# untitled.net
KiCad netlist of a schematic drawn in EAGLE
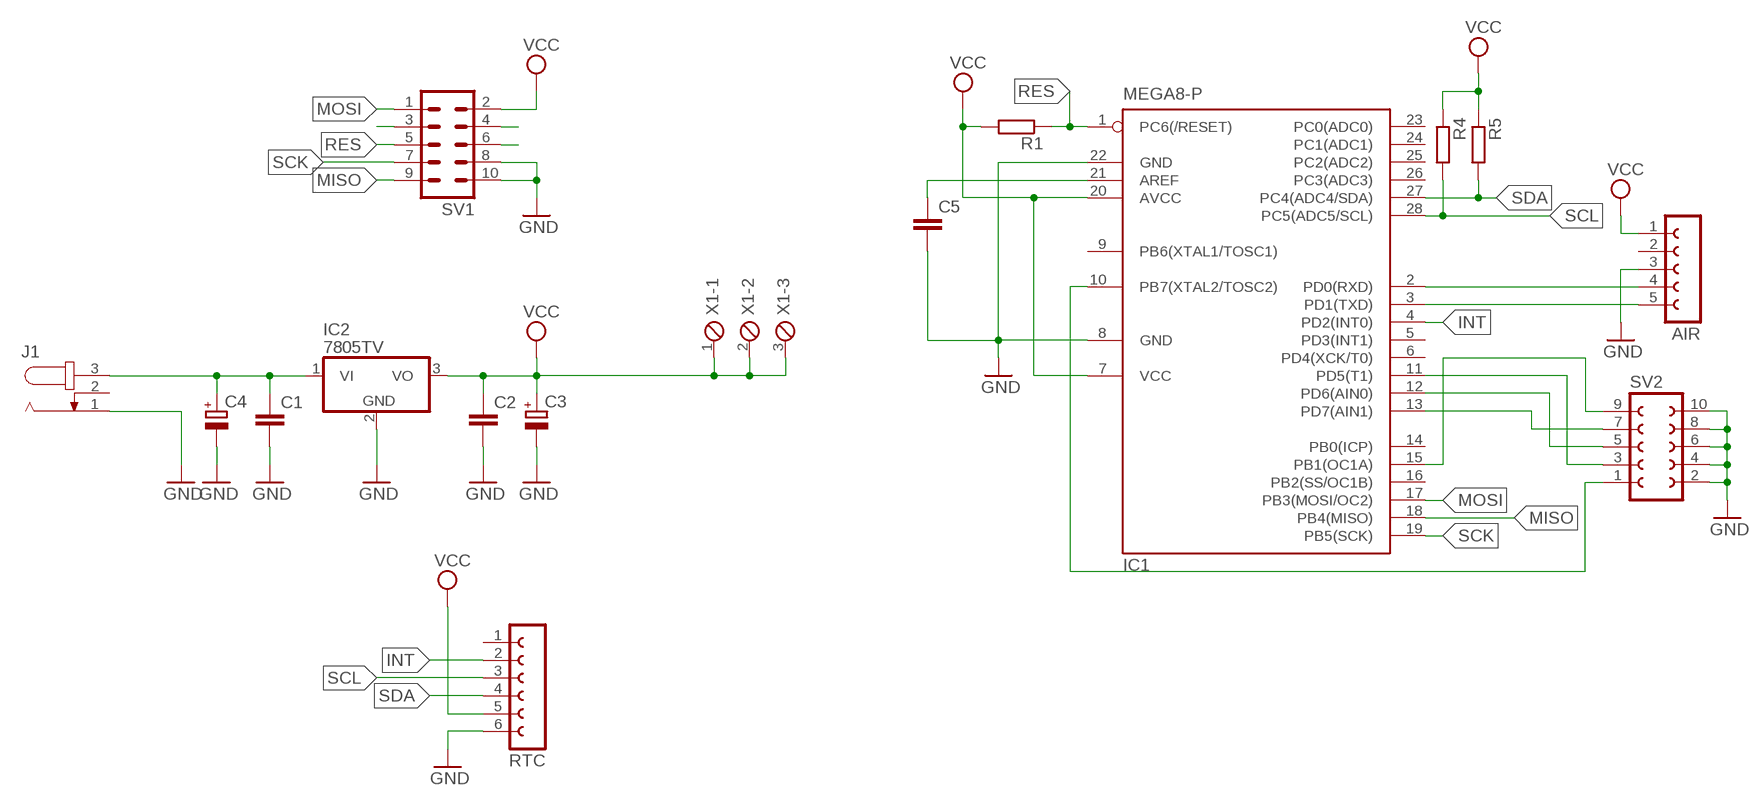
[diagram p0: schematic, sheet 1]

(export (version "E")
  (design (tool "Eeschema 10.0.6"))
  (components
    (comp (ref "AIR")
      (value "FE05-1")
      (footprint "eagle-import:FE05-1")
      (libsource (lib "eagle-import") (part "FE05-1"))
    )
    (comp (ref "C1")
      (value "C-EU025-025X050")
      (footprint "eagle-import:C025-025X050")
      (libsource (lib "eagle-import") (part "C-EU025-025X050"))
    )
    (comp (ref "C2")
      (value "C-EU025-025X050")
      (footprint "eagle-import:C025-025X050")
      (libsource (lib "eagle-import") (part "C-EU025-025X050"))
    )
    (comp (ref "C3")
      (value "CPOL-EUE2.5-5")
      (footprint "eagle-import:E2,5-5")
      (libsource (lib "eagle-import") (part "CPOL-EUE2.5-5"))
    )
    (comp (ref "C4")
      (value "CPOL-EUE3.5-8")
      (footprint "eagle-import:E3,5-8")
      (libsource (lib "eagle-import") (part "CPOL-EUE3.5-8"))
    )
    (comp (ref "C5")
      (value "C-EU025-025X050")
      (footprint "eagle-import:C025-025X050")
      (libsource (lib "eagle-import") (part "C-EU025-025X050"))
    )
    (comp (ref "IC1")
      (value "MEGA8-P")
      (footprint "eagle-import:DIL28-3")
      (libsource (lib "eagle-import") (part "MEGA8-P"))
    )
    (comp (ref "IC2")
      (value "7805TV")
      (footprint "eagle-import:TO220V")
      (libsource (lib "eagle-import") (part "78TV05"))
    )
    (comp (ref "J1")
      (value "JACK-PLUG1")
      (footprint "eagle-import:SPC4078")
      (libsource (lib "eagle-import") (part "JACK-PLUG1"))
    )
    (comp (ref "R1")
      (value "R-EU_0207/7")
      (footprint "eagle-import:0207_7")
      (libsource (lib "eagle-import") (part "R-EU_0207/7"))
    )
    (comp (ref "R4")
      (value "R-EU_0207/7")
      (footprint "eagle-import:0207_7")
      (libsource (lib "eagle-import") (part "R-EU_0207/7"))
    )
    (comp (ref "R5")
      (value "R-EU_0207/7")
      (footprint "eagle-import:0207_7")
      (libsource (lib "eagle-import") (part "R-EU_0207/7"))
    )
    (comp (ref "RTC")
      (value "FE06-1")
      (footprint "eagle-import:FE06")
      (libsource (lib "eagle-import") (part "FE06-1"))
    )
    (comp (ref "SV1")
      (value "ML10")
      (footprint "eagle-import:ML10")
      (libsource (lib "eagle-import") (part "ML10"))
    )
    (comp (ref "SV2")
      (value "FE05-2")
      (footprint "eagle-import:FE05-2")
      (libsource (lib "eagle-import") (part "FE05-2"))
    )
    (comp (ref "X1")
      (value "MPT3")
      (footprint "eagle-import:3POL254")
      (libsource (lib "eagle-import") (part "MPT3"))
    )
  )
  (nets
    (net (code "1") (name "GND") (class "Default")
      (node (ref "AIR") (pin "3") (pinfunction "3_3") (pintype "passive"))
      (node (ref "C1") (pin "2") (pinfunction "2_2") (pintype "passive"))
      (node (ref "C2") (pin "2") (pinfunction "2_2") (pintype "passive"))
      (node (ref "C3") (pin "-") (pinfunction "-_-") (pintype "passive"))
      (node (ref "C4") (pin "-") (pinfunction "-_-") (pintype "passive"))
      (node (ref "C5") (pin "2") (pinfunction "2_2") (pintype "passive"))
      (node (ref "IC1") (pin "22") (pinfunction "GND_22") (pintype "power_in"))
      (node (ref "IC1") (pin "8") (pinfunction "GND_8") (pintype "power_in"))
      (node (ref "IC2") (pin "2") (pinfunction "GND_2") (pintype "passive"))
      (node (ref "J1") (pin "1") (pinfunction "1_1") (pintype "passive"))
      (node (ref "RTC") (pin "6") (pinfunction "6_6") (pintype "passive"))
      (node (ref "SV1") (pin "10") (pinfunction "10_10") (pintype "passive"))
      (node (ref "SV1") (pin "8") (pinfunction "8_8") (pintype "passive"))
      (node (ref "SV2") (pin "10") (pinfunction "10_10") (pintype "passive"))
      (node (ref "SV2") (pin "2") (pinfunction "2_2") (pintype "passive"))
      (node (ref "SV2") (pin "4") (pinfunction "4_4") (pintype "passive"))
      (node (ref "SV2") (pin "6") (pinfunction "6_6") (pintype "passive"))
      (node (ref "SV2") (pin "8") (pinfunction "8_8") (pintype "passive"))
    )
    (net (code "2") (name "INT") (class "Default")
      (node (ref "IC1") (pin "4") (pinfunction "PD2(INT0)_4") (pintype "bidirectional"))
      (node (ref "RTC") (pin "2") (pinfunction "2_2") (pintype "passive"))
    )
    (net (code "3") (name "MISO") (class "Default")
      (node (ref "IC1") (pin "18") (pinfunction "PB4(MISO)_18") (pintype "bidirectional"))
      (node (ref "SV1") (pin "9") (pinfunction "9_9") (pintype "passive"))
    )
    (net (code "4") (name "MOSI") (class "Default")
      (node (ref "IC1") (pin "17") (pinfunction "PB3(MOSI/OC2)_17") (pintype "bidirectional"))
      (node (ref "SV1") (pin "1") (pinfunction "1_1") (pintype "passive"))
    )
    (net (code "5") (name "Net-(IC1-AREF)") (class "Default")
      (node (ref "C5") (pin "1") (pinfunction "1_1") (pintype "passive"))
      (node (ref "IC1") (pin "21") (pinfunction "AREF_21") (pintype "passive"))
    )
    (net (code "6") (name "Net-(IC1-PB1(OC1A))") (class "Default")
      (node (ref "IC1") (pin "15") (pinfunction "PB1(OC1A)_15") (pintype "bidirectional"))
      (node (ref "SV2") (pin "9") (pinfunction "9_9") (pintype "passive"))
    )
    (net (code "7") (name "Net-(IC1-PB7(XTAL2{slash}TOSC2))") (class "Default")
      (node (ref "IC1") (pin "10") (pinfunction "PB7(XTAL2/TOSC2)_10") (pintype "bidirectional"))
      (node (ref "SV2") (pin "1") (pinfunction "1_1") (pintype "passive"))
    )
    (net (code "8") (name "Net-(IC1-PD0(RXD))") (class "Default")
      (node (ref "AIR") (pin "4") (pinfunction "4_4") (pintype "passive"))
      (node (ref "IC1") (pin "2") (pinfunction "PD0(RXD)_2") (pintype "bidirectional"))
    )
    (net (code "9") (name "Net-(IC1-PD1(TXD))") (class "Default")
      (node (ref "AIR") (pin "5") (pinfunction "5_5") (pintype "passive"))
      (node (ref "IC1") (pin "3") (pinfunction "PD1(TXD)_3") (pintype "bidirectional"))
    )
    (net (code "10") (name "Net-(IC1-PD5(T1))") (class "Default")
      (node (ref "IC1") (pin "11") (pinfunction "PD5(T1)_11") (pintype "bidirectional"))
      (node (ref "SV2") (pin "3") (pinfunction "3_3") (pintype "passive"))
    )
    (net (code "11") (name "Net-(IC1-PD6(AIN0))") (class "Default")
      (node (ref "IC1") (pin "12") (pinfunction "PD6(AIN0)_12") (pintype "bidirectional"))
      (node (ref "SV2") (pin "5") (pinfunction "5_5") (pintype "passive"))
    )
    (net (code "12") (name "Net-(IC1-PD7(AIN1))") (class "Default")
      (node (ref "IC1") (pin "13") (pinfunction "PD7(AIN1)_13") (pintype "bidirectional"))
      (node (ref "SV2") (pin "7") (pinfunction "7_7") (pintype "passive"))
    )
    (net (code "13") (name "Net-(IC2-VI)") (class "Default")
      (node (ref "C1") (pin "1") (pinfunction "1_1") (pintype "passive"))
      (node (ref "C4") (pin "+") (pinfunction "+_+") (pintype "passive"))
      (node (ref "IC2") (pin "1") (pinfunction "VI_1") (pintype "input"))
      (node (ref "J1") (pin "3") (pinfunction "3_3") (pintype "passive"))
    )
    (net (code "14") (name "RES") (class "Default")
      (node (ref "IC1") (pin "1") (pinfunction "PC6(/RESET)_1") (pintype "bidirectional"))
      (node (ref "R1") (pin "1") (pinfunction "1_1") (pintype "passive"))
      (node (ref "SV1") (pin "5") (pinfunction "5_5") (pintype "passive"))
    )
    (net (code "15") (name "SCK") (class "Default")
      (node (ref "IC1") (pin "19") (pinfunction "PB5(SCK)_19") (pintype "bidirectional"))
      (node (ref "SV1") (pin "7") (pinfunction "7_7") (pintype "passive"))
    )
    (net (code "16") (name "SCL") (class "Default")
      (node (ref "IC1") (pin "28") (pinfunction "PC5(ADC5/SCL)_28") (pintype "bidirectional"))
      (node (ref "R4") (pin "2") (pinfunction "2_2") (pintype "passive"))
      (node (ref "RTC") (pin "3") (pinfunction "3_3") (pintype "passive"))
    )
    (net (code "17") (name "SDA") (class "Default")
      (node (ref "IC1") (pin "27") (pinfunction "PC4(ADC4/SDA)_27") (pintype "bidirectional"))
      (node (ref "R5") (pin "2") (pinfunction "2_2") (pintype "passive"))
      (node (ref "RTC") (pin "4") (pinfunction "4_4") (pintype "passive"))
    )
    (net (code "18") (name "VCC") (class "Default")
      (node (ref "AIR") (pin "1") (pinfunction "1_1") (pintype "passive"))
      (node (ref "C2") (pin "1") (pinfunction "1_1") (pintype "passive"))
      (node (ref "C3") (pin "+") (pinfunction "+_+") (pintype "passive"))
      (node (ref "IC1") (pin "20") (pinfunction "AVCC_20") (pintype "power_in"))
      (node (ref "IC1") (pin "7") (pinfunction "VCC_7") (pintype "power_in"))
      (node (ref "IC2") (pin "3") (pinfunction "VO_3") (pintype "passive"))
      (node (ref "R1") (pin "2") (pinfunction "2_2") (pintype "passive"))
      (node (ref "R4") (pin "1") (pinfunction "1_1") (pintype "passive"))
      (node (ref "R5") (pin "1") (pinfunction "1_1") (pintype "passive"))
      (node (ref "RTC") (pin "5") (pinfunction "5_5") (pintype "passive"))
      (node (ref "SV1") (pin "2") (pinfunction "2_2") (pintype "passive"))
      (node (ref "X1") (pin "1") (pinfunction "1_1") (pintype "passive"))
      (node (ref "X1") (pin "2") (pinfunction "1_2") (pintype "passive"))
      (node (ref "X1") (pin "3") (pinfunction "1_3") (pintype "passive"))
    )
    (net (code "19") (name "unconnected-(AIR-Pad2)") (class "Default")
      (node (ref "AIR") (pin "2") (pinfunction "2_2") (pintype "passive"))
    )
    (net (code "20") (name "unconnected-(IC1-PB0(ICP)-Pad14)") (class "Default")
      (node (ref "IC1") (pin "14") (pinfunction "PB0(ICP)_14") (pintype "bidirectional"))
    )
    (net (code "21") (name "unconnected-(IC1-PB2(SS{slash}OC1B)-Pad16)") (class "Default")
      (node (ref "IC1") (pin "16") (pinfunction "PB2(SS/OC1B)_16") (pintype "bidirectional"))
    )
    (net (code "22") (name "unconnected-(IC1-PB6(XTAL1{slash}TOSC1)-Pad9)") (class "Default")
      (node (ref "IC1") (pin "9") (pinfunction "PB6(XTAL1/TOSC1)_9") (pintype "bidirectional"))
    )
    (net (code "23") (name "unconnected-(IC1-PC0(ADC0)-Pad23)") (class "Default")
      (node (ref "IC1") (pin "23") (pinfunction "PC0(ADC0)_23") (pintype "bidirectional"))
    )
    (net (code "24") (name "unconnected-(IC1-PC1(ADC1)-Pad24)") (class "Default")
      (node (ref "IC1") (pin "24") (pinfunction "PC1(ADC1)_24") (pintype "bidirectional"))
    )
    (net (code "25") (name "unconnected-(IC1-PC2(ADC2)-Pad25)") (class "Default")
      (node (ref "IC1") (pin "25") (pinfunction "PC2(ADC2)_25") (pintype "bidirectional"))
    )
    (net (code "26") (name "unconnected-(IC1-PC3(ADC3)-Pad26)") (class "Default")
      (node (ref "IC1") (pin "26") (pinfunction "PC3(ADC3)_26") (pintype "bidirectional"))
    )
    (net (code "27") (name "unconnected-(IC1-PD3(INT1)-Pad5)") (class "Default")
      (node (ref "IC1") (pin "5") (pinfunction "PD3(INT1)_5") (pintype "bidirectional"))
    )
    (net (code "28") (name "unconnected-(IC1-PD4(XCK{slash}T0)-Pad6)") (class "Default")
      (node (ref "IC1") (pin "6") (pinfunction "PD4(XCK/T0)_6") (pintype "bidirectional"))
    )
    (net (code "29") (name "unconnected-(J1-Pad2)") (class "Default")
      (node (ref "J1") (pin "2") (pinfunction "2_2") (pintype "passive"))
    )
    (net (code "30") (name "unconnected-(RTC-Pad1)") (class "Default")
      (node (ref "RTC") (pin "1") (pinfunction "1_1") (pintype "passive"))
    )
    (net (code "31") (name "unconnected-(SV1-Pad3)") (class "Default")
      (node (ref "SV1") (pin "3") (pinfunction "3_3") (pintype "passive"))
    )
    (net (code "32") (name "unconnected-(SV1-Pad4)") (class "Default")
      (node (ref "SV1") (pin "4") (pinfunction "4_4") (pintype "passive"))
    )
    (net (code "33") (name "unconnected-(SV1-Pad6)") (class "Default")
      (node (ref "SV1") (pin "6") (pinfunction "6_6") (pintype "passive"))
    )
  )
)
